# edge-lord-2000.net
KiCad netlist of a schematic drawn in EAGLE
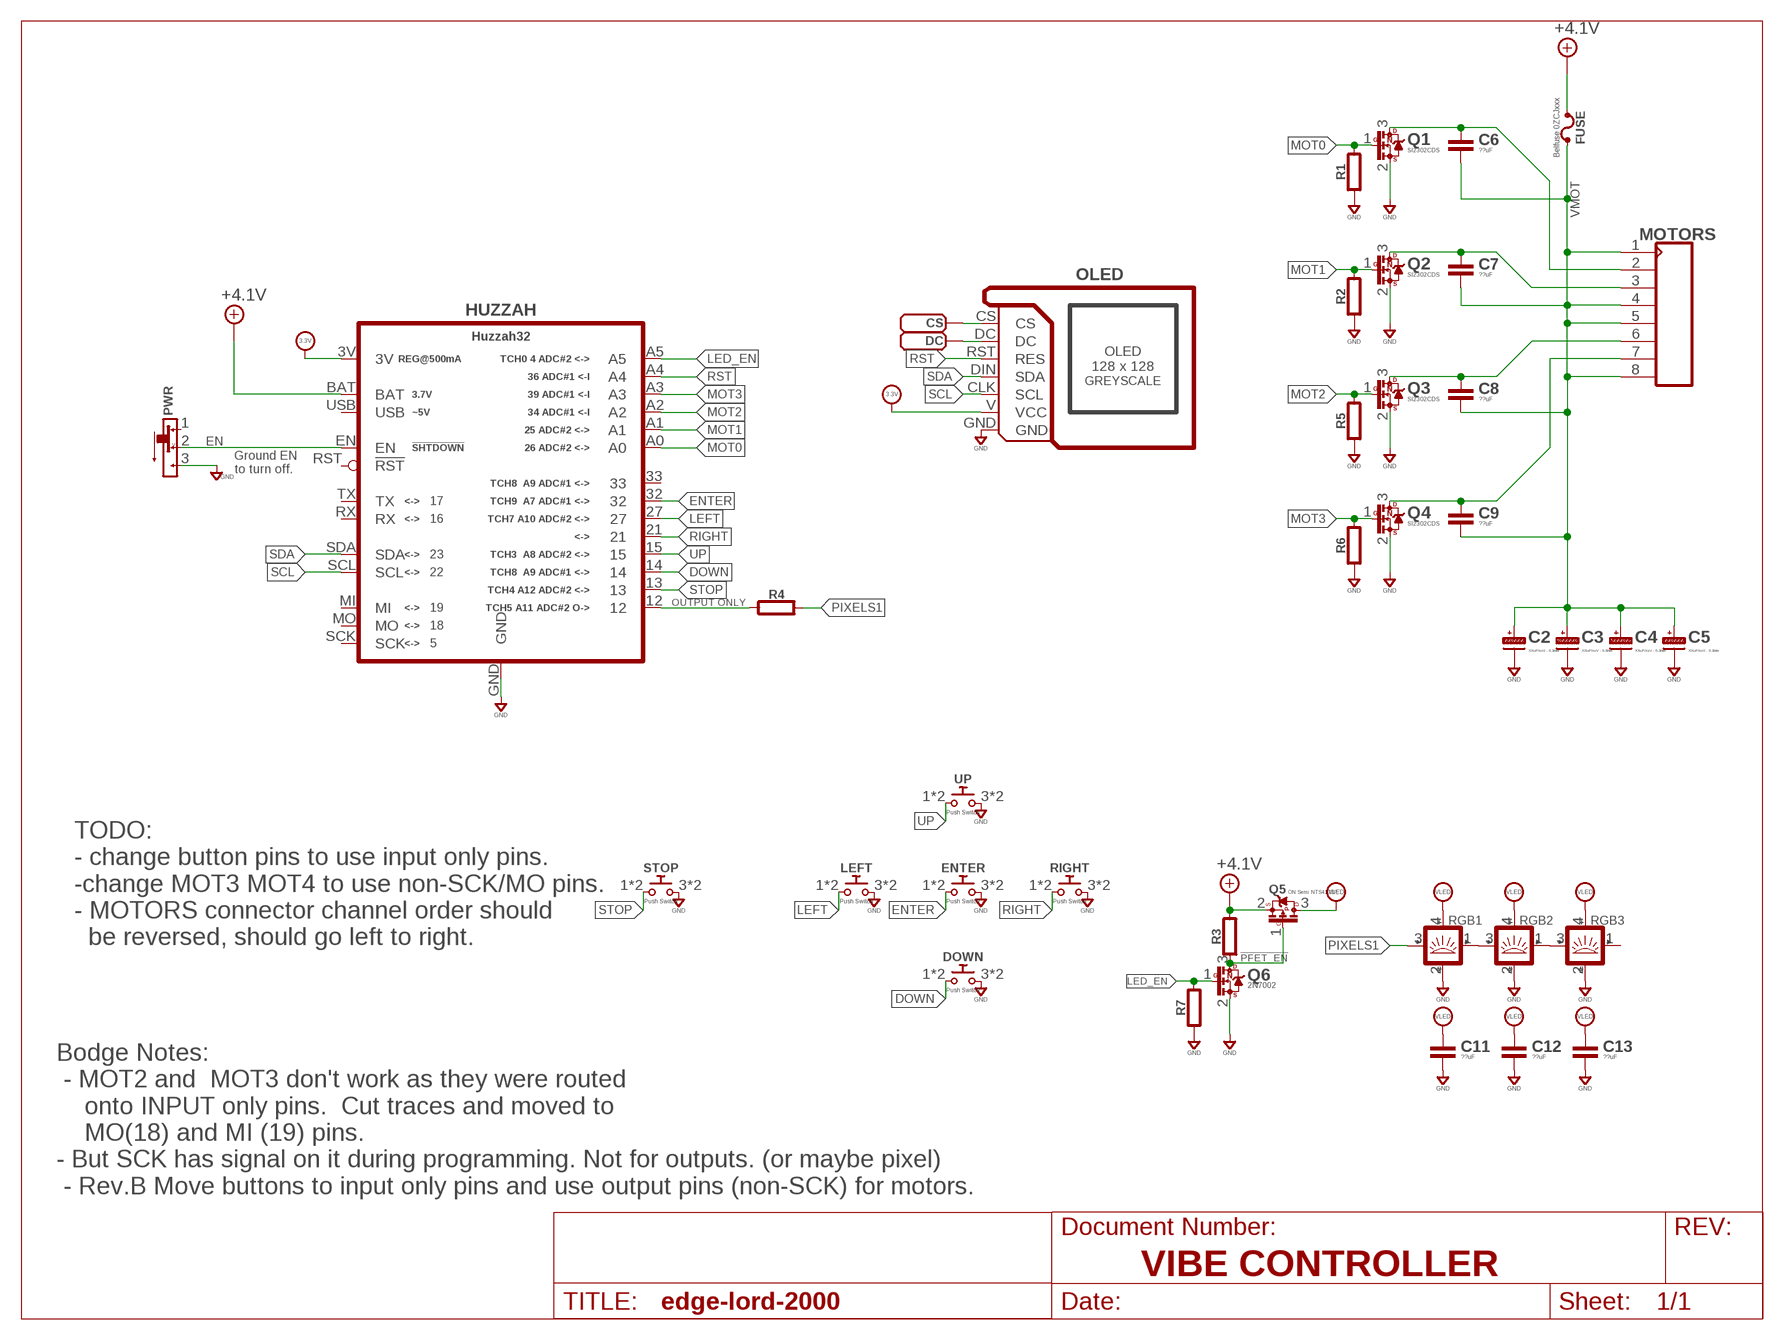
[diagram p0: schematic, sheet 1]

(export (version "E")
  (design (tool "Eeschema 10.0.6"))
  (components
    (comp (ref "C2")
      (value "XXuF/xxV - 6.3mm")
      (footprint "eagle-import:CAP_ALUM_SMT_6.3")
      (libsource (lib "eagle-import") (part "CAPACITOR_POL-ALUM-SMT-6.3"))
    )
    (comp (ref "C3")
      (value "XXuF/xxV - 6.3mm")
      (footprint "eagle-import:CAP_ALUM_SMT_6.3")
      (libsource (lib "eagle-import") (part "CAPACITOR_POL-ALUM-SMT-6.3"))
    )
    (comp (ref "C4")
      (value "XXuF/xxV - 6.3mm")
      (footprint "eagle-import:CAP_ALUM_SMT_6.3")
      (libsource (lib "eagle-import") (part "CAPACITOR_POL-ALUM-SMT-6.3"))
    )
    (comp (ref "C5")
      (value "XXuF/xxV - 6.3mm")
      (footprint "eagle-import:CAP_ALUM_SMT_6.3")
      (libsource (lib "eagle-import") (part "CAPACITOR_POL-ALUM-SMT-6.3"))
    )
    (comp (ref "C6")
      (value "??uF")
      (footprint "eagle-import:0603-CAP")
      (libsource (lib "eagle-import") (part "CAPACITOR0603"))
    )
    (comp (ref "C7")
      (value "??uF")
      (footprint "eagle-import:0603-CAP")
      (libsource (lib "eagle-import") (part "CAPACITOR0603"))
    )
    (comp (ref "C8")
      (value "??uF")
      (footprint "eagle-import:0603-CAP")
      (libsource (lib "eagle-import") (part "CAPACITOR0603"))
    )
    (comp (ref "C9")
      (value "??uF")
      (footprint "eagle-import:0603-CAP")
      (libsource (lib "eagle-import") (part "CAPACITOR0603"))
    )
    (comp (ref "C11")
      (value "??uF")
      (footprint "eagle-import:0603-CAP")
      (libsource (lib "eagle-import") (part "CAPACITOR0603"))
    )
    (comp (ref "C12")
      (value "??uF")
      (footprint "eagle-import:0603-CAP")
      (libsource (lib "eagle-import") (part "CAPACITOR0603"))
    )
    (comp (ref "C13")
      (value "??uF")
      (footprint "eagle-import:0603-CAP")
      (libsource (lib "eagle-import") (part "CAPACITOR0603"))
    )
    (comp (ref "CS")
      (value "PADSMD-070X070")
      (footprint "eagle-import:SMD-070MIL")
      (libsource (lib "eagle-import") (part "PADSMD-070X070"))
    )
    (comp (ref "DC")
      (value "PADSMD-070X070")
      (footprint "eagle-import:SMD-070MIL")
      (libsource (lib "eagle-import") (part "PADSMD-070X070"))
    )
    (comp (ref "DOWN")
      (value "Push Switch")
      (footprint "eagle-import:B3SN")
      (fields (field (name "MFR") "Omron") (field (name "MPN") "B3SN"))
      (libsource (lib "eagle-import") (part "PUSHBTN-MOMB3SN"))
    )
    (comp (ref "ENTER")
      (value "Push Switch")
      (footprint "eagle-import:B3SN")
      (fields (field (name "MFR") "Omron") (field (name "MPN") "B3SN"))
      (libsource (lib "eagle-import") (part "PUSHBTN-MOMB3SN"))
    )
    (comp (ref "FUSE")
      (value "Belfuse 0ZCJxxx")
      (footprint "eagle-import:BELFUSE-1206")
      (libsource (lib "eagle-import") (part "FUSEPOLY-1206"))
    )
    (comp (ref "HUZZAH")
      (value "Huzzah32")
      (footprint "eagle-import:ADAFRUIT_HUZZAH32")
      (libsource (lib "eagle-import") (part "HUZZAHHUZZAH"))
    )
    (comp (ref "LEFT")
      (value "Push Switch")
      (footprint "eagle-import:B3SN")
      (fields (field (name "MFR") "Omron") (field (name "MPN") "B3SN"))
      (libsource (lib "eagle-import") (part "PUSHBTN-MOMB3SN"))
    )
    (comp (ref "MOTORS")
      (value "CON_08X1-RA-THD")
      (footprint "eagle-import:MA08X1-RA-THD")
      (libsource (lib "eagle-import") (part "CON_08X1-RA-THD"))
    )
    (comp (ref "OLED")
      (value "GREYSCALE")
      (footprint "eagle-import:SSD1327-THD-MODULE")
      (fields (field (name "MFR") "Amazon") (field (name "MPN") "B079NNZ9V1"))
      (libsource (lib "eagle-import") (part "OLED_128X128_MODULE-128X128-MONO-30MM"))
    )
    (comp (ref "PWR")
      (value "SLIDE-SPDTJS102011JCQN")
      (footprint "eagle-import:CK_JS102011JCQN")
      (libsource (lib "eagle-import") (part "SLIDE-SPDTJS102011JCQN"))
    )
    (comp (ref "Q1")
      (value "SI2302CDS")
      (footprint "eagle-import:SOT-23")
      (libsource (lib "eagle-import") (part "N-FET_SI2302"))
    )
    (comp (ref "Q2")
      (value "SI2302CDS")
      (footprint "eagle-import:SOT-23")
      (libsource (lib "eagle-import") (part "N-FET_SI2302"))
    )
    (comp (ref "Q3")
      (value "SI2302CDS")
      (footprint "eagle-import:SOT-23")
      (libsource (lib "eagle-import") (part "N-FET_SI2302"))
    )
    (comp (ref "Q4")
      (value "SI2302CDS")
      (footprint "eagle-import:SOT-23")
      (libsource (lib "eagle-import") (part "N-FET_SI2302"))
    )
    (comp (ref "Q5")
      (value "ON Semi NTS4173P")
      (footprint "eagle-import:SOT-323")
      (fields (field (name "MFR") "ONsemi") (field (name "MPN") "NTS4173"))
      (libsource (lib "eagle-import") (part "P-FETSOT-323"))
    )
    (comp (ref "Q6")
      (value "2N7002")
      (footprint "eagle-import:SOT-23")
      (libsource (lib "eagle-import") (part "N-FET_2N7002"))
    )
    (comp (ref "R1")
      (value "100K")
      (footprint "eagle-import:0603-RES")
      (libsource (lib "eagle-import") (part "RESISTOR0603"))
    )
    (comp (ref "R2")
      (value "100K")
      (footprint "eagle-import:0603-RES")
      (libsource (lib "eagle-import") (part "RESISTOR0603"))
    )
    (comp (ref "R3")
      (value "20K")
      (footprint "eagle-import:0603-RES")
      (libsource (lib "eagle-import") (part "RESISTOR0603"))
    )
    (comp (ref "R4")
      (value "330")
      (footprint "eagle-import:0603-RES")
      (libsource (lib "eagle-import") (part "RESISTOR0603"))
    )
    (comp (ref "R5")
      (value "100K")
      (footprint "eagle-import:0603-RES")
      (libsource (lib "eagle-import") (part "RESISTOR0603"))
    )
    (comp (ref "R6")
      (value "100K")
      (footprint "eagle-import:0603-RES")
      (libsource (lib "eagle-import") (part "RESISTOR0603"))
    )
    (comp (ref "R7")
      (value "100K")
      (footprint "eagle-import:0603-RES")
      (libsource (lib "eagle-import") (part "RESISTOR0603"))
    )
    (comp (ref "RGB1")
      (value "SMART_LED3535")
      (footprint "eagle-import:SMD_3535")
      (libsource (lib "eagle-import") (part "SMART_LED3535"))
    )
    (comp (ref "RGB2")
      (value "SMART_LED3535")
      (footprint "eagle-import:SMD_3535")
      (libsource (lib "eagle-import") (part "SMART_LED3535"))
    )
    (comp (ref "RGB3")
      (value "SMART_LED3535")
      (footprint "eagle-import:SMD_3535")
      (libsource (lib "eagle-import") (part "SMART_LED3535"))
    )
    (comp (ref "RIGHT")
      (value "Push Switch")
      (footprint "eagle-import:B3SN")
      (fields (field (name "MFR") "Omron") (field (name "MPN") "B3SN"))
      (libsource (lib "eagle-import") (part "PUSHBTN-MOMB3SN"))
    )
    (comp (ref "STOP")
      (value "Push Switch")
      (footprint "eagle-import:B3SN")
      (fields (field (name "MFR") "Omron") (field (name "MPN") "B3SN"))
      (libsource (lib "eagle-import") (part "PUSHBTN-MOMB3SN"))
    )
    (comp (ref "UP")
      (value "Push Switch")
      (footprint "eagle-import:B3SN")
      (fields (field (name "MFR") "Omron") (field (name "MPN") "B3SN"))
      (libsource (lib "eagle-import") (part "PUSHBTN-MOMB3SN"))
    )
  )
  (nets
    (net (code "1") (name "+4.1V") (class "Default")
      (node (ref "FUSE") (pin "1") (pinfunction "1_1") (pintype "bidirectional"))
      (node (ref "HUZZAH") (pin "BAT") (pinfunction "BAT_BAT") (pintype "bidirectional"))
      (node (ref "Q5") (pin "2") (pinfunction "S_2") (pintype "bidirectional"))
      (node (ref "R3") (pin "2") (pinfunction "2_2") (pintype "passive"))
    )
    (net (code "2") (name "/EN") (class "Default")
      (node (ref "HUZZAH") (pin "EN") (pinfunction "EN_EN") (pintype "bidirectional"))
      (node (ref "PWR") (pin "2") (pinfunction "2_2") (pintype "bidirectional"))
    )
    (net (code "3") (name "/VMOT") (class "Default")
      (node (ref "C2") (pin "+") (pinfunction "P_+") (pintype "bidirectional"))
      (node (ref "C3") (pin "+") (pinfunction "P_+") (pintype "bidirectional"))
      (node (ref "C4") (pin "+") (pinfunction "P_+") (pintype "bidirectional"))
      (node (ref "C5") (pin "+") (pinfunction "P_+") (pintype "bidirectional"))
      (node (ref "C6") (pin "2") (pinfunction "2_2") (pintype "passive"))
      (node (ref "C7") (pin "2") (pinfunction "2_2") (pintype "passive"))
      (node (ref "C8") (pin "2") (pinfunction "2_2") (pintype "passive"))
      (node (ref "C9") (pin "2") (pinfunction "2_2") (pintype "passive"))
      (node (ref "FUSE") (pin "2") (pinfunction "2_2") (pintype "bidirectional"))
      (node (ref "MOTORS") (pin "1") (pinfunction "1_1") (pintype "passive"))
      (node (ref "MOTORS") (pin "4") (pinfunction "4_4") (pintype "passive"))
      (node (ref "MOTORS") (pin "5") (pinfunction "5_5") (pintype "passive"))
      (node (ref "MOTORS") (pin "8") (pinfunction "8_8") (pintype "passive"))
    )
    (net (code "4") (name "/~{PFET_EN}") (class "Default")
      (node (ref "Q5") (pin "1") (pinfunction "G_1") (pintype "bidirectional"))
      (node (ref "Q6") (pin "3") (pinfunction "D_3") (pintype "bidirectional"))
      (node (ref "R3") (pin "1") (pinfunction "1_1") (pintype "passive"))
    )
    (net (code "5") (name "3.3V") (class "Default")
      (node (ref "HUZZAH") (pin "3V") (pinfunction "3V_3V") (pintype "bidirectional"))
      (node (ref "OLED") (pin "V") (pinfunction "VCC_V") (pintype "bidirectional"))
    )
    (net (code "6") (name "DOWN") (class "Default")
      (node (ref "DOWN") (pin "1") (pinfunction "1_1") (pintype "passive"))
      (node (ref "DOWN") (pin "2") (pinfunction "1_2") (pintype "passive"))
      (node (ref "HUZZAH") (pin "14") (pinfunction "14_14") (pintype "bidirectional"))
    )
    (net (code "7") (name "ENTER") (class "Default")
      (node (ref "ENTER") (pin "1") (pinfunction "1_1") (pintype "passive"))
      (node (ref "ENTER") (pin "2") (pinfunction "1_2") (pintype "passive"))
      (node (ref "HUZZAH") (pin "32") (pinfunction "32_32") (pintype "bidirectional"))
    )
    (net (code "8") (name "GND") (class "Default")
      (node (ref "C11") (pin "2") (pinfunction "2_2") (pintype "passive"))
      (node (ref "C12") (pin "2") (pinfunction "2_2") (pintype "passive"))
      (node (ref "C13") (pin "2") (pinfunction "2_2") (pintype "passive"))
      (node (ref "C2") (pin "-") (pinfunction "N_-") (pintype "bidirectional"))
      (node (ref "C3") (pin "-") (pinfunction "N_-") (pintype "bidirectional"))
      (node (ref "C4") (pin "-") (pinfunction "N_-") (pintype "bidirectional"))
      (node (ref "C5") (pin "-") (pinfunction "N_-") (pintype "bidirectional"))
      (node (ref "DOWN") (pin "3") (pinfunction "2_3") (pintype "passive"))
      (node (ref "DOWN") (pin "4") (pinfunction "2_4") (pintype "passive"))
      (node (ref "ENTER") (pin "3") (pinfunction "2_3") (pintype "passive"))
      (node (ref "ENTER") (pin "4") (pinfunction "2_4") (pintype "passive"))
      (node (ref "HUZZAH") (pin "GND") (pinfunction "GND_GND") (pintype "bidirectional"))
      (node (ref "LEFT") (pin "3") (pinfunction "2_3") (pintype "passive"))
      (node (ref "LEFT") (pin "4") (pinfunction "2_4") (pintype "passive"))
      (node (ref "OLED") (pin "GND") (pinfunction "GND_GND") (pintype "bidirectional"))
      (node (ref "PWR") (pin "3") (pinfunction "3_3") (pintype "bidirectional"))
      (node (ref "Q1") (pin "2") (pinfunction "S_2") (pintype "bidirectional"))
      (node (ref "Q2") (pin "2") (pinfunction "S_2") (pintype "bidirectional"))
      (node (ref "Q3") (pin "2") (pinfunction "S_2") (pintype "bidirectional"))
      (node (ref "Q4") (pin "2") (pinfunction "S_2") (pintype "bidirectional"))
      (node (ref "Q6") (pin "2") (pinfunction "S_2") (pintype "bidirectional"))
      (node (ref "R1") (pin "1") (pinfunction "1_1") (pintype "passive"))
      (node (ref "R2") (pin "1") (pinfunction "1_1") (pintype "passive"))
      (node (ref "R5") (pin "1") (pinfunction "1_1") (pintype "passive"))
      (node (ref "R6") (pin "1") (pinfunction "1_1") (pintype "passive"))
      (node (ref "R7") (pin "1") (pinfunction "1_1") (pintype "passive"))
      (node (ref "RGB1") (pin "2") (pinfunction "GND_2") (pintype "bidirectional"))
      (node (ref "RGB2") (pin "2") (pinfunction "GND_2") (pintype "bidirectional"))
      (node (ref "RGB3") (pin "2") (pinfunction "GND_2") (pintype "bidirectional"))
      (node (ref "RIGHT") (pin "3") (pinfunction "2_3") (pintype "passive"))
      (node (ref "RIGHT") (pin "4") (pinfunction "2_4") (pintype "passive"))
      (node (ref "STOP") (pin "3") (pinfunction "2_3") (pintype "passive"))
      (node (ref "STOP") (pin "4") (pinfunction "2_4") (pintype "passive"))
      (node (ref "UP") (pin "3") (pinfunction "2_3") (pintype "passive"))
      (node (ref "UP") (pin "4") (pinfunction "2_4") (pintype "passive"))
    )
    (net (code "9") (name "LED_EN") (class "Default")
      (node (ref "HUZZAH") (pin "A5") (pinfunction "A5_A5") (pintype "bidirectional"))
      (node (ref "Q6") (pin "1") (pinfunction "G_1") (pintype "bidirectional"))
      (node (ref "R7") (pin "2") (pinfunction "2_2") (pintype "passive"))
    )
    (net (code "10") (name "LEFT") (class "Default")
      (node (ref "HUZZAH") (pin "27") (pinfunction "27_27") (pintype "bidirectional"))
      (node (ref "LEFT") (pin "1") (pinfunction "1_1") (pintype "passive"))
      (node (ref "LEFT") (pin "2") (pinfunction "1_2") (pintype "passive"))
    )
    (net (code "11") (name "MOT0") (class "Default")
      (node (ref "HUZZAH") (pin "A0") (pinfunction "A0_A0") (pintype "bidirectional"))
      (node (ref "Q1") (pin "1") (pinfunction "G_1") (pintype "bidirectional"))
      (node (ref "R1") (pin "2") (pinfunction "2_2") (pintype "passive"))
    )
    (net (code "12") (name "MOT1") (class "Default")
      (node (ref "HUZZAH") (pin "A1") (pinfunction "A1_A1") (pintype "bidirectional"))
      (node (ref "Q2") (pin "1") (pinfunction "G_1") (pintype "bidirectional"))
      (node (ref "R2") (pin "2") (pinfunction "2_2") (pintype "passive"))
    )
    (net (code "13") (name "MOT2") (class "Default")
      (node (ref "HUZZAH") (pin "A2") (pinfunction "A2_A2") (pintype "bidirectional"))
      (node (ref "Q3") (pin "1") (pinfunction "G_1") (pintype "bidirectional"))
      (node (ref "R5") (pin "2") (pinfunction "2_2") (pintype "passive"))
    )
    (net (code "14") (name "MOT3") (class "Default")
      (node (ref "HUZZAH") (pin "A3") (pinfunction "A3_A3") (pintype "bidirectional"))
      (node (ref "Q4") (pin "1") (pinfunction "G_1") (pintype "bidirectional"))
      (node (ref "R6") (pin "2") (pinfunction "2_2") (pintype "passive"))
    )
    (net (code "15") (name "Net-(CS-PAD)") (class "Default")
      (node (ref "CS") (pin "1") (pinfunction "PAD_1") (pintype "bidirectional"))
      (node (ref "OLED") (pin "CS") (pinfunction "CS_CS") (pintype "bidirectional"))
    )
    (net (code "16") (name "Net-(DC-PAD)") (class "Default")
      (node (ref "DC") (pin "1") (pinfunction "PAD_1") (pintype "bidirectional"))
      (node (ref "OLED") (pin "DC") (pinfunction "DC_DC") (pintype "bidirectional"))
    )
    (net (code "17") (name "Net-(HUZZAH-Pad12)") (class "Default")
      (node (ref "HUZZAH") (pin "12") (pinfunction "12_12") (pintype "bidirectional"))
      (node (ref "R4") (pin "1") (pinfunction "1_1") (pintype "passive"))
    )
    (net (code "18") (name "Net-(Q1-D)") (class "Default")
      (node (ref "C6") (pin "1") (pinfunction "1_1") (pintype "passive"))
      (node (ref "MOTORS") (pin "2") (pinfunction "2_2") (pintype "passive"))
      (node (ref "Q1") (pin "3") (pinfunction "D_3") (pintype "bidirectional"))
    )
    (net (code "19") (name "Net-(Q2-D)") (class "Default")
      (node (ref "C7") (pin "1") (pinfunction "1_1") (pintype "passive"))
      (node (ref "MOTORS") (pin "3") (pinfunction "3_3") (pintype "passive"))
      (node (ref "Q2") (pin "3") (pinfunction "D_3") (pintype "bidirectional"))
    )
    (net (code "20") (name "Net-(Q3-D)") (class "Default")
      (node (ref "C8") (pin "1") (pinfunction "1_1") (pintype "passive"))
      (node (ref "MOTORS") (pin "6") (pinfunction "6_6") (pintype "passive"))
      (node (ref "Q3") (pin "3") (pinfunction "D_3") (pintype "bidirectional"))
    )
    (net (code "21") (name "Net-(Q4-D)") (class "Default")
      (node (ref "C9") (pin "1") (pinfunction "1_1") (pintype "passive"))
      (node (ref "MOTORS") (pin "7") (pinfunction "7_7") (pintype "passive"))
      (node (ref "Q4") (pin "3") (pinfunction "D_3") (pintype "bidirectional"))
    )
    (net (code "22") (name "Net-(RGB1-OUT)") (class "Default")
      (node (ref "RGB1") (pin "1") (pinfunction "OUT_1") (pintype "bidirectional"))
      (node (ref "RGB2") (pin "3") (pinfunction "IN_3") (pintype "bidirectional"))
    )
    (net (code "23") (name "Net-(RGB2-OUT)") (class "Default")
      (node (ref "RGB2") (pin "1") (pinfunction "OUT_1") (pintype "bidirectional"))
      (node (ref "RGB3") (pin "3") (pinfunction "IN_3") (pintype "bidirectional"))
    )
    (net (code "24") (name "PIXELS1") (class "Default")
      (node (ref "R4") (pin "2") (pinfunction "2_2") (pintype "passive"))
      (node (ref "RGB1") (pin "3") (pinfunction "IN_3") (pintype "bidirectional"))
    )
    (net (code "25") (name "RIGHT") (class "Default")
      (node (ref "HUZZAH") (pin "21") (pinfunction "21_21") (pintype "bidirectional"))
      (node (ref "RIGHT") (pin "1") (pinfunction "1_1") (pintype "passive"))
      (node (ref "RIGHT") (pin "2") (pinfunction "1_2") (pintype "passive"))
    )
    (net (code "26") (name "RST") (class "Default")
      (node (ref "HUZZAH") (pin "A4") (pinfunction "A4_A4") (pintype "bidirectional"))
      (node (ref "OLED") (pin "RST") (pinfunction "RES_RST") (pintype "bidirectional"))
    )
    (net (code "27") (name "SCL") (class "Default")
      (node (ref "HUZZAH") (pin "SCL") (pinfunction "SCL_SCL") (pintype "bidirectional"))
      (node (ref "OLED") (pin "CLK") (pinfunction "SCL_CLK") (pintype "bidirectional"))
    )
    (net (code "28") (name "SDA") (class "Default")
      (node (ref "HUZZAH") (pin "SDA") (pinfunction "SDA_SDA") (pintype "bidirectional"))
      (node (ref "OLED") (pin "DIN") (pinfunction "SDA_DIN") (pintype "bidirectional"))
    )
    (net (code "29") (name "STOP") (class "Default")
      (node (ref "HUZZAH") (pin "13") (pinfunction "13_13") (pintype "bidirectional"))
      (node (ref "STOP") (pin "1") (pinfunction "1_1") (pintype "passive"))
      (node (ref "STOP") (pin "2") (pinfunction "1_2") (pintype "passive"))
    )
    (net (code "30") (name "UP") (class "Default")
      (node (ref "HUZZAH") (pin "15") (pinfunction "15_15") (pintype "bidirectional"))
      (node (ref "UP") (pin "1") (pinfunction "1_1") (pintype "passive"))
      (node (ref "UP") (pin "2") (pinfunction "1_2") (pintype "passive"))
    )
    (net (code "31") (name "VLED") (class "Default")
      (node (ref "C11") (pin "1") (pinfunction "1_1") (pintype "passive"))
      (node (ref "C12") (pin "1") (pinfunction "1_1") (pintype "passive"))
      (node (ref "C13") (pin "1") (pinfunction "1_1") (pintype "passive"))
      (node (ref "Q5") (pin "3") (pinfunction "D_3") (pintype "bidirectional"))
      (node (ref "RGB1") (pin "4") (pinfunction "VDD_4") (pintype "bidirectional"))
      (node (ref "RGB2") (pin "4") (pinfunction "VDD_4") (pintype "bidirectional"))
      (node (ref "RGB3") (pin "4") (pinfunction "VDD_4") (pintype "bidirectional"))
    )
    (net (code "32") (name "unconnected-(HUZZAH-Pad33)") (class "Default")
      (node (ref "HUZZAH") (pin "33") (pinfunction "33_33") (pintype "bidirectional"))
    )
    (net (code "33") (name "unconnected-(HUZZAH-PadMI)") (class "Default")
      (node (ref "HUZZAH") (pin "MI") (pinfunction "MI_MI") (pintype "bidirectional"))
    )
    (net (code "34") (name "unconnected-(HUZZAH-PadMO)") (class "Default")
      (node (ref "HUZZAH") (pin "MO") (pinfunction "MO_MO") (pintype "bidirectional"))
    )
    (net (code "35") (name "unconnected-(HUZZAH-PadRX)") (class "Default")
      (node (ref "HUZZAH") (pin "RX") (pinfunction "RX_RX") (pintype "bidirectional"))
    )
    (net (code "36") (name "unconnected-(HUZZAH-PadSCK)") (class "Default")
      (node (ref "HUZZAH") (pin "SCK") (pinfunction "SCK_SCK") (pintype "bidirectional"))
    )
    (net (code "37") (name "unconnected-(HUZZAH-PadTX)") (class "Default")
      (node (ref "HUZZAH") (pin "TX") (pinfunction "TX_TX") (pintype "bidirectional"))
    )
    (net (code "38") (name "unconnected-(HUZZAH-PadUSB)") (class "Default")
      (node (ref "HUZZAH") (pin "USB") (pinfunction "USB_USB") (pintype "bidirectional"))
    )
    (net (code "39") (name "unconnected-(HUZZAH-~{RST}-PadRST)") (class "Default")
      (node (ref "HUZZAH") (pin "RST") (pinfunction "~{RST}_RST") (pintype "bidirectional"))
    )
    (net (code "40") (name "unconnected-(PWR-Pad1)") (class "Default")
      (node (ref "PWR") (pin "1") (pinfunction "1_1") (pintype "bidirectional"))
    )
    (net (code "41") (name "unconnected-(RGB3-OUT-Pad1)") (class "Default")
      (node (ref "RGB3") (pin "1") (pinfunction "OUT_1") (pintype "bidirectional"))
    )
  )
)
